# 5V_Output_shift.net
KiCad netlist of a schematic drawn in Altium Designer
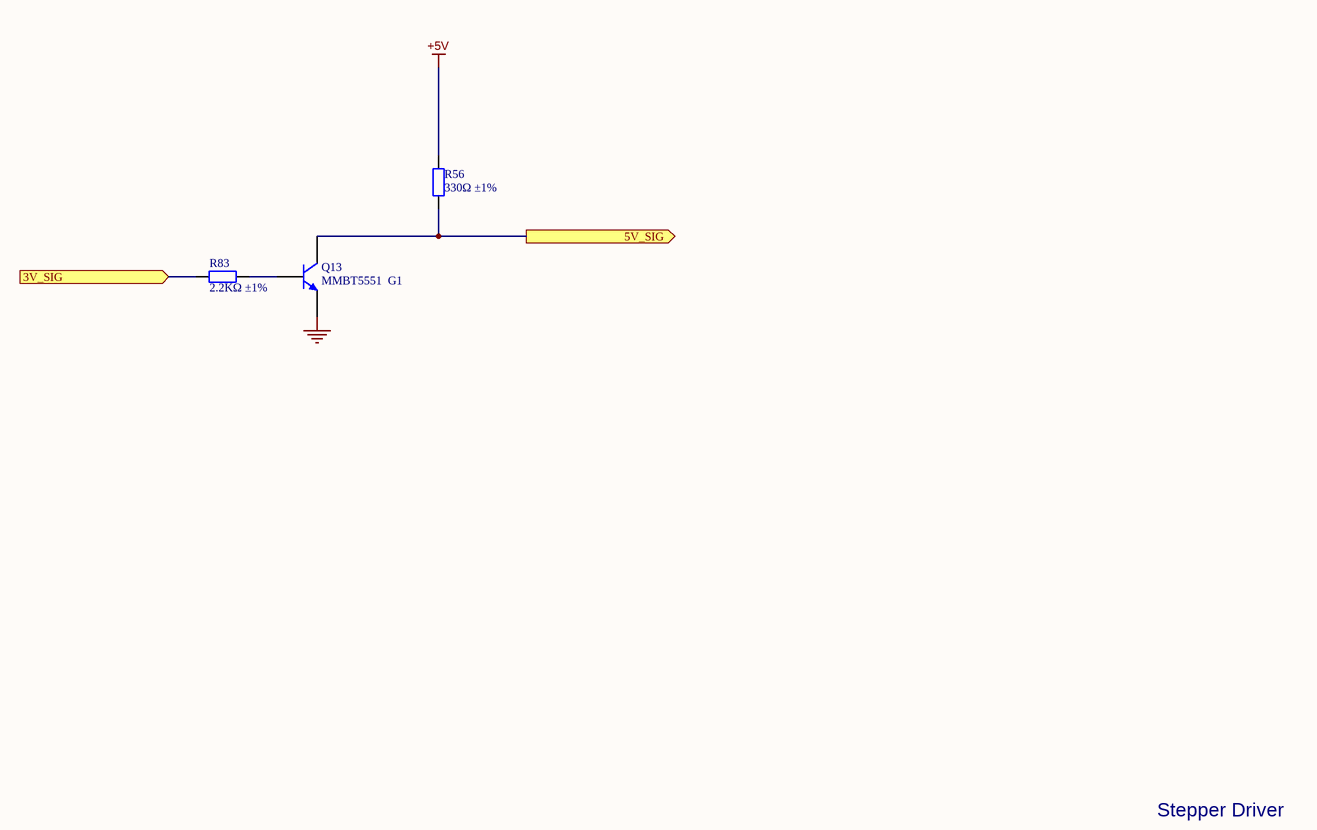
[diagram p0: 5V_Output_shift.SchDoc]

(export (version "E")
  (design (tool "Eeschema 10.0.6"))
  (components
    (comp (ref "Q13")
      (value "MMBT5551  G1")
      (footprint "SOT-23(SOT-23-3)")
      (description "三极管")
      (libsource (lib "Transistor_NPN") (part "SOT-23 MMBT5551  G1"))
    )
    (comp (ref "R56")
      (value "330Ω ±1%")
      (footprint "0402_R")
      (description "Chip resistor")
      (fields (field (name "MANUFACTURER") "Uniroyal Elec") (field (name "PARTNUMBER") "0402WGF3300TCE"))
      (libsource (lib "RES") (part "0402 330R (3300) 1%"))
    )
    (comp (ref "R83")
      (value "2.2KΩ ±1%")
      (footprint "0402_R")
      (description "Chip resistor")
      (fields (field (name "MANUFACTURER") "Uniroyal Elec") (field (name "PARTNUMBER") "0402WGF2201TCE"))
      (libsource (lib "RES") (part "0402 2.2K (2201) 1%"))
    )
  )
  (nets
    (net (code "1") (name "+5V") (class "Default")
      (node (ref "R56") (pin "2") (pinfunction "2_2") (pintype "passive"))
    )
    (net (code "2") (name "/3V_SIG") (class "Default")
      (node (ref "R83") (pin "1") (pinfunction "1_1") (pintype "passive"))
    )
    (net (code "3") (name "/5V_SIG") (class "Default")
      (node (ref "Q13") (pin "3") (pinfunction "C_3") (pintype "passive"))
      (node (ref "R56") (pin "1") (pinfunction "1_1") (pintype "passive"))
    )
    (net (code "4") (name "GND") (class "Default")
      (node (ref "Q13") (pin "2") (pinfunction "E_2") (pintype "passive"))
    )
    (net (code "5") (name "Net-(Q13-B)") (class "Default")
      (node (ref "Q13") (pin "1") (pinfunction "B_1") (pintype "passive"))
      (node (ref "R83") (pin "2") (pinfunction "2_2") (pintype "passive"))
    )
  )
)
